# galvo_driver.net
KiCad netlist of a schematic drawn in Altium Designer
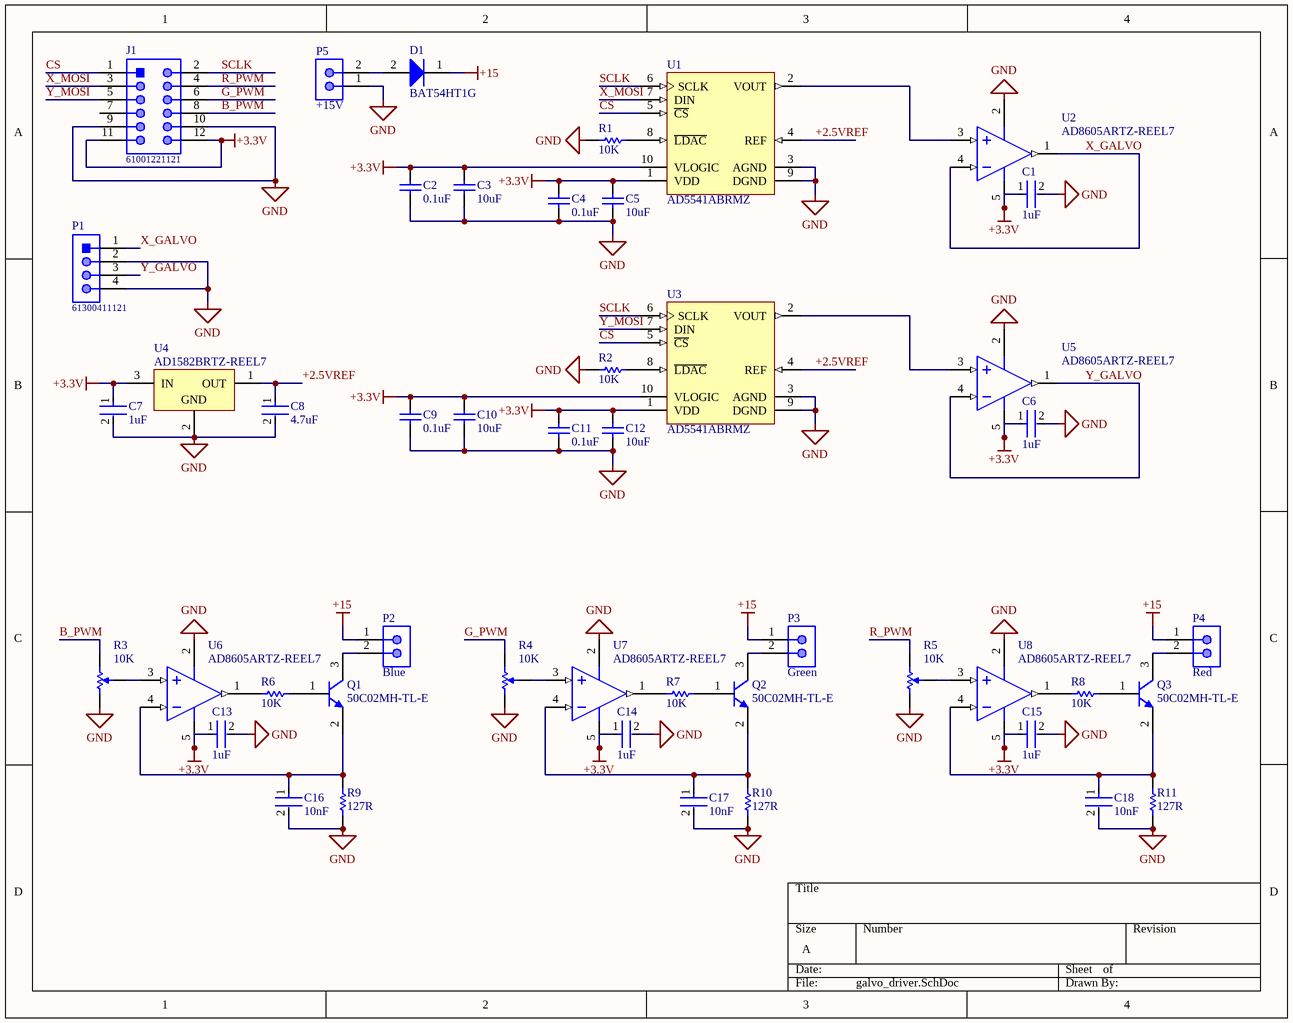
[diagram p0: galvo_driver.SchDoc]

(export (version "E")
  (design (tool "Eeschema 10.0.6"))
  (components
    (comp (ref "C1")
      (value "1uF")
      (footprint "FP-CC0603-DA-MFG")
      (description "CAP CER 1UF 16V X7R 0603")
      (fields (field (name "TOLERANCE") "0.1") (field (name "MANUFACTURER") "YAGEO"))
      (libsource (lib "Altium Content Vault") (part "11868f565c42a9108669ba33697ecf6"))
    )
    (comp (ref "C2")
      (value "0.1uF")
      (footprint "CAPC1608X87X35NL15T15")
      (description "C0603X104K5RACTU")
      (fields (field (name "MANUFACTURER") "Kemet"))
      (libsource (lib "Altium Content Vault") (part "CAP"))
    )
    (comp (ref "C3")
      (value "10uF")
      (footprint "CAPC1608X90X35NL10T15")
      (description "GRM188R60J106ME47D")
      (fields (field (name "MANUFACTURER") "Murata"))
      (libsource (lib "Altium Content Vault") (part "CAP"))
    )
    (comp (ref "C4")
      (value "0.1uF")
      (footprint "CAPC1608X87X35NL15T15")
      (description "C0603X104K5RACTU")
      (fields (field (name "MANUFACTURER") "Kemet"))
      (libsource (lib "Altium Content Vault") (part "CAP"))
    )
    (comp (ref "C5")
      (value "10uF")
      (footprint "CAPC1608X90X35NL10T15")
      (description "GRM188R60J106ME47D")
      (fields (field (name "MANUFACTURER") "Murata"))
      (libsource (lib "Altium Content Vault") (part "CAP"))
    )
    (comp (ref "C6")
      (value "1uF")
      (footprint "FP-CC0603-DA-MFG")
      (description "CAP CER 1UF 16V X7R 0603")
      (fields (field (name "TOLERANCE") "0.1") (field (name "MANUFACTURER") "YAGEO"))
      (libsource (lib "Altium Content Vault") (part "11868f565c42a9108669ba33697ecf6"))
    )
    (comp (ref "C7")
      (value "1uF")
      (footprint "FP-CC0603-DA-MFG")
      (description "CAP CER 1UF 16V X7R 0603")
      (fields (field (name "TOLERANCE") "0.1") (field (name "MANUFACTURER") "YAGEO"))
      (libsource (lib "Altium Content Vault") (part "11868f565c42a9108669ba33697ecf6"))
    )
    (comp (ref "C8")
      (value "4.7uF")
      (footprint "FP-C0603-CG-MFG")
      (description "CAP CER 4.7UF 6.3V X5R 0603")
      (fields (field (name "TOLERANCE") "10%") (field (name "MANUFACTURER") "Kemet"))
      (libsource (lib "Altium Content Vault") (part "11868f565c42a9108669ba33697ecf6"))
    )
    (comp (ref "C9")
      (value "0.1uF")
      (footprint "CAPC1608X87X35NL15T15")
      (description "C0603X104K5RACTU")
      (fields (field (name "MANUFACTURER") "Kemet"))
      (libsource (lib "Altium Content Vault") (part "CAP"))
    )
    (comp (ref "C10")
      (value "10uF")
      (footprint "CAPC1608X90X35NL10T15")
      (description "GRM188R60J106ME47D")
      (fields (field (name "MANUFACTURER") "Murata"))
      (libsource (lib "Altium Content Vault") (part "CAP"))
    )
    (comp (ref "C11")
      (value "0.1uF")
      (footprint "CAPC1608X87X35NL15T15")
      (description "C0603X104K5RACTU")
      (fields (field (name "MANUFACTURER") "Kemet"))
      (libsource (lib "Altium Content Vault") (part "CAP"))
    )
    (comp (ref "C12")
      (value "10uF")
      (footprint "CAPC1608X90X35NL10T15")
      (description "GRM188R60J106ME47D")
      (fields (field (name "MANUFACTURER") "Murata"))
      (libsource (lib "Altium Content Vault") (part "CAP"))
    )
    (comp (ref "C13")
      (value "1uF")
      (footprint "FP-CC0603-DA-MFG")
      (description "CAP CER 1UF 16V X7R 0603")
      (fields (field (name "TOLERANCE") "0.1") (field (name "MANUFACTURER") "YAGEO"))
      (libsource (lib "Altium Content Vault") (part "11868f565c42a9108669ba33697ecf6"))
    )
    (comp (ref "C14")
      (value "1uF")
      (footprint "FP-CC0603-DA-MFG")
      (description "CAP CER 1UF 16V X7R 0603")
      (fields (field (name "TOLERANCE") "0.1") (field (name "MANUFACTURER") "YAGEO"))
      (libsource (lib "Altium Content Vault") (part "11868f565c42a9108669ba33697ecf6"))
    )
    (comp (ref "C15")
      (value "1uF")
      (footprint "FP-CC0603-DA-MFG")
      (description "CAP CER 1UF 16V X7R 0603")
      (fields (field (name "TOLERANCE") "0.1") (field (name "MANUFACTURER") "YAGEO"))
      (libsource (lib "Altium Content Vault") (part "11868f565c42a9108669ba33697ecf6"))
    )
    (comp (ref "C16")
      (value "10nF")
      (footprint "FP-CGA3E-0_3-0_1-IPC_A")
      (description "Cap Ceramic 10nF 100V X8R 10% Pad SMD 0603 +150°C Automotive T/R")
      (fields (field (name "TOLERANCE") "10%"))
      (libsource (lib "Altium Content Vault") (part "b4654b650e69147ec39a6b967a45e02"))
    )
    (comp (ref "C17")
      (value "10nF")
      (footprint "FP-CGA3E-0_3-0_1-IPC_A")
      (description "Cap Ceramic 10nF 100V X8R 10% Pad SMD 0603 +150°C Automotive T/R")
      (fields (field (name "TOLERANCE") "10%"))
      (libsource (lib "Altium Content Vault") (part "b4654b650e69147ec39a6b967a45e02"))
    )
    (comp (ref "C18")
      (value "10nF")
      (footprint "FP-CGA3E-0_3-0_1-IPC_A")
      (description "Cap Ceramic 10nF 100V X8R 10% Pad SMD 0603 +150°C Automotive T/R")
      (fields (field (name "TOLERANCE") "10%"))
      (libsource (lib "Altium Content Vault") (part "b4654b650e69147ec39a6b967a45e02"))
    )
    (comp (ref "D1")
      (value "BAT54HT1G")
      (footprint "ONSC-SOD-323-2-477-02_V")
      (description "Schottky Barrier Diode, 2-Pin SOD-323, Pb-Free, Tape and Reel")
      (fields (field (name "MANUFACTURER") "On Semiconductor"))
      (libsource (lib "Altium Content Vault") (part "ONSC-D-K1A2-2"))
    )
    (comp (ref "J1")
      (value "61001221121")
      (footprint "61001221121")
      (description "SMT Vertical Pin Header WR-PHD, Pitch 2.54 mm, Dual Row, 12 pins")
      (fields (field (name "MANUFACTURER") "Wurth Elektronik") (field (name "PUBLISHER") "WurthElektronik"))
      (libsource (lib "Altium Content Vault") (part "WE-CN-2P-M-R12"))
    )
    (comp (ref "P1")
      (value "61300411121")
      (footprint "61300411121")
      (description "THT Vertical Pin Header WR-PHD, Pitch 2.54 mm, Single Row, 4 pins")
      (fields (field (name "MANUFACTURER") "Wurth Elektronik") (field (name "PUBLISHER") "WurthElektronik"))
      (libsource (lib "Altium Content Vault") (part "WE-CN-1P-M-R4"))
    )
    (comp (ref "P2")
      (value "Blue")
      (footprint "JST-B2B-XH-A_V")
      (fields (field (name "MANUFACTURER") "JST"))
      (libsource (lib "Altium Content Vault") (part "CN-1P-M-R2"))
    )
    (comp (ref "P3")
      (value "Green")
      (footprint "JST-B2B-XH-A_V")
      (fields (field (name "MANUFACTURER") "JST"))
      (libsource (lib "Altium Content Vault") (part "CN-1P-M-R2"))
    )
    (comp (ref "P4")
      (value "Red")
      (footprint "JST-B2B-XH-A_V")
      (fields (field (name "MANUFACTURER") "JST"))
      (libsource (lib "Altium Content Vault") (part "CN-1P-M-R2"))
    )
    (comp (ref "P5")
      (value "+15V")
      (footprint "JST-B2B-XH-A_V")
      (fields (field (name "MANUFACTURER") "JST"))
      (libsource (lib "") (part "CN-1P-M-R2_1"))
    )
    (comp (ref "Q1")
      (value "50C02MH-TL-E")
      (footprint "ONSC-MCPH-3_V")
      (description "Bipolar Transistor, 50 V, 0.5 A, Low VCE(sat), NPN Single, 3-Pin MCPH, Pb-Free, Tape and Reel")
      (fields (field (name "MANUFACTURER") "On Semiconductor"))
      (libsource (lib "Altium Content Vault") (part "ONSC-NPN-B1E2C3-3"))
    )
    (comp (ref "Q2")
      (value "50C02MH-TL-E")
      (footprint "ONSC-MCPH-3_V")
      (description "Bipolar Transistor, 50 V, 0.5 A, Low VCE(sat), NPN Single, 3-Pin MCPH, Pb-Free, Tape and Reel")
      (fields (field (name "MANUFACTURER") "On Semiconductor"))
      (libsource (lib "Altium Content Vault") (part "ONSC-NPN-B1E2C3-3"))
    )
    (comp (ref "Q3")
      (value "50C02MH-TL-E")
      (footprint "ONSC-MCPH-3_V")
      (description "Bipolar Transistor, 50 V, 0.5 A, Low VCE(sat), NPN Single, 3-Pin MCPH, Pb-Free, Tape and Reel")
      (fields (field (name "MANUFACTURER") "On Semiconductor"))
      (libsource (lib "Altium Content Vault") (part "ONSC-NPN-B1E2C3-3"))
    )
    (comp (ref "R1")
      (value "10K")
      (footprint "RESC1609X55X30LL15T15")
      (description "Chip Resistor, 10 KOhm, +/- 1%, 0.1 W, -55 to 155 degC, 0603 (1608 Metric), RoHS, Tape and Reel")
      (fields (field (name "TOLERANCE") "1%") (field (name "MANUFACTURER") "Panasonic"))
      (libsource (lib "Altium Content Vault") (part "RES-2"))
    )
    (comp (ref "R2")
      (value "10K")
      (footprint "RESC1609X55X30LL15T15")
      (description "Chip Resistor, 10 KOhm, +/- 1%, 0.1 W, -55 to 155 degC, 0603 (1608 Metric), RoHS, Tape and Reel")
      (fields (field (name "TOLERANCE") "1%") (field (name "MANUFACTURER") "Panasonic"))
      (libsource (lib "Altium Content Vault") (part "RES-2"))
    )
    (comp (ref "R3")
      (value "10K")
      (footprint "BOUR-3313J-1_V")
      (description "Trimming Potentiometer, 10 KOhm, -55 to 125 degC, 3-Pin SMD, RoHS, Tape and Reel")
      (fields (field (name "MANUFACTURER") "Bourns"))
      (libsource (lib "Altium Content Vault") (part "RES-ADJ-3_A"))
    )
    (comp (ref "R4")
      (value "10K")
      (footprint "BOUR-3313J-1_V")
      (description "Trimming Potentiometer, 10 KOhm, -55 to 125 degC, 3-Pin SMD, RoHS, Tape and Reel")
      (fields (field (name "MANUFACTURER") "Bourns"))
      (libsource (lib "Altium Content Vault") (part "RES-ADJ-3_A"))
    )
    (comp (ref "R5")
      (value "10K")
      (footprint "BOUR-3313J-1_V")
      (description "Trimming Potentiometer, 10 KOhm, -55 to 125 degC, 3-Pin SMD, RoHS, Tape and Reel")
      (fields (field (name "MANUFACTURER") "Bourns"))
      (libsource (lib "Altium Content Vault") (part "RES-ADJ-3_A"))
    )
    (comp (ref "R6")
      (value "10K")
      (footprint "RESC1609X55X30LL15T15")
      (description "Chip Resistor, 10 KOhm, +/- 1%, 0.1 W, -55 to 155 degC, 0603 (1608 Metric), RoHS, Tape and Reel")
      (fields (field (name "TOLERANCE") "1%") (field (name "MANUFACTURER") "Panasonic"))
      (libsource (lib "Altium Content Vault") (part "RES-2"))
    )
    (comp (ref "R7")
      (value "10K")
      (footprint "RESC1609X55X30LL15T15")
      (description "Chip Resistor, 10 KOhm, +/- 1%, 0.1 W, -55 to 155 degC, 0603 (1608 Metric), RoHS, Tape and Reel")
      (fields (field (name "TOLERANCE") "1%") (field (name "MANUFACTURER") "Panasonic"))
      (libsource (lib "Altium Content Vault") (part "RES-2"))
    )
    (comp (ref "R8")
      (value "10K")
      (footprint "RESC1609X55X30LL15T15")
      (description "Chip Resistor, 10 KOhm, +/- 1%, 0.1 W, -55 to 155 degC, 0603 (1608 Metric), RoHS, Tape and Reel")
      (fields (field (name "TOLERANCE") "1%") (field (name "MANUFACTURER") "Panasonic"))
      (libsource (lib "Altium Content Vault") (part "RES-2"))
    )
    (comp (ref "R9")
      (value "127R")
      (footprint "RESC1608X55X30LL15T15")
      (description "ERJ-3EKF1270V")
      (fields (field (name "MANUFACTURER") "Panasonic"))
      (libsource (lib "Altium Content Vault") (part "RES"))
    )
    (comp (ref "R10")
      (value "127R")
      (footprint "RESC1608X55X30LL15T15")
      (description "ERJ-3EKF1270V")
      (fields (field (name "MANUFACTURER") "Panasonic"))
      (libsource (lib "Altium Content Vault") (part "RES"))
    )
    (comp (ref "R11")
      (value "127R")
      (footprint "RESC1608X55X30LL15T15")
      (description "ERJ-3EKF1270V")
      (fields (field (name "MANUFACTURER") "Panasonic"))
      (libsource (lib "Altium Content Vault") (part "RES"))
    )
    (comp (ref "U1")
      (value "AD5541ABRMZ")
      (footprint "RM-10_L")
      (fields (field (name "GENERIC PART NUMBER") "AD5541A") (field (name "MANUFACTURER") "Analog Devices"))
      (libsource (lib "Altium Content Vault") (part "ADI-AD5541A-RM-10"))
    )
    (comp (ref "U2")
      (value "AD8605ARTZ-REEL7")
      (footprint "ADI-RJ-5_M")
      (fields (field (name "MANUFACTURER") "Analog Devices") (field (name "GENERIC PART NUMBER") "AD8605"))
      (libsource (lib "Altium Content Vault") (part "ADI-ADxxxx-X-5"))
    )
    (comp (ref "U3")
      (value "AD5541ABRMZ")
      (footprint "RM-10_L")
      (fields (field (name "GENERIC PART NUMBER") "AD5541A") (field (name "MANUFACTURER") "Analog Devices"))
      (libsource (lib "Altium Content Vault") (part "ADI-AD5541A-RM-10"))
    )
    (comp (ref "U4")
      (value "AD1582BRTZ-REEL7")
      (footprint "ADI-RT-3_M")
      (fields (field (name "MANUFACTURER") "Analog Devices"))
      (libsource (lib "Altium Content Vault") (part "ADI-AD158X-RT-3"))
    )
    (comp (ref "U5")
      (value "AD8605ARTZ-REEL7")
      (footprint "ADI-RJ-5_M")
      (fields (field (name "MANUFACTURER") "Analog Devices") (field (name "GENERIC PART NUMBER") "AD8605"))
      (libsource (lib "Altium Content Vault") (part "ADI-ADxxxx-X-5"))
    )
    (comp (ref "U6")
      (value "AD8605ARTZ-REEL7")
      (footprint "ADI-RJ-5_M")
      (fields (field (name "MANUFACTURER") "Analog Devices") (field (name "GENERIC PART NUMBER") "AD8605"))
      (libsource (lib "Altium Content Vault") (part "ADI-ADxxxx-X-5"))
    )
    (comp (ref "U7")
      (value "AD8605ARTZ-REEL7")
      (footprint "ADI-RJ-5_M")
      (fields (field (name "MANUFACTURER") "Analog Devices") (field (name "GENERIC PART NUMBER") "AD8605"))
      (libsource (lib "Altium Content Vault") (part "ADI-ADxxxx-X-5"))
    )
    (comp (ref "U8")
      (value "AD8605ARTZ-REEL7")
      (footprint "ADI-RJ-5_M")
      (fields (field (name "MANUFACTURER") "Analog Devices") (field (name "GENERIC PART NUMBER") "AD8605"))
      (libsource (lib "Altium Content Vault") (part "ADI-ADxxxx-X-5"))
    )
  )
  (nets
    (net (code "1") (name "+3.3V") (class "Default")
      (node (ref "C1") (pin "1") (pinfunction "1_1") (pintype "passive"))
      (node (ref "C10") (pin "2") (pinfunction "2_2") (pintype "passive"))
      (node (ref "C11") (pin "1") (pinfunction "1_1") (pintype "passive"))
      (node (ref "C12") (pin "2") (pinfunction "2_2") (pintype "passive"))
      (node (ref "C13") (pin "1") (pinfunction "1_1") (pintype "passive"))
      (node (ref "C14") (pin "1") (pinfunction "1_1") (pintype "passive"))
      (node (ref "C15") (pin "1") (pinfunction "1_1") (pintype "passive"))
      (node (ref "C2") (pin "1") (pinfunction "1_1") (pintype "passive"))
      (node (ref "C3") (pin "2") (pinfunction "2_2") (pintype "passive"))
      (node (ref "C4") (pin "1") (pinfunction "1_1") (pintype "passive"))
      (node (ref "C5") (pin "2") (pinfunction "2_2") (pintype "passive"))
      (node (ref "C6") (pin "1") (pinfunction "1_1") (pintype "passive"))
      (node (ref "C7") (pin "1") (pinfunction "1_1") (pintype "passive"))
      (node (ref "C9") (pin "1") (pinfunction "1_1") (pintype "passive"))
      (node (ref "J1") (pin "11") (pinfunction "11_11") (pintype "passive"))
      (node (ref "J1") (pin "12") (pinfunction "12_12") (pintype "passive"))
      (node (ref "U1") (pin "1") (pinfunction "VDD_1") (pintype "power_in"))
      (node (ref "U1") (pin "10") (pinfunction "VLOGIC_10") (pintype "power_in"))
      (node (ref "U2") (pin "5") (pinfunction "+V_5") (pintype "power_in"))
      (node (ref "U3") (pin "1") (pinfunction "VDD_1") (pintype "power_in"))
      (node (ref "U3") (pin "10") (pinfunction "VLOGIC_10") (pintype "power_in"))
      (node (ref "U4") (pin "3") (pinfunction "IN_3") (pintype "power_in"))
      (node (ref "U5") (pin "5") (pinfunction "+V_5") (pintype "power_in"))
      (node (ref "U6") (pin "5") (pinfunction "+V_5") (pintype "power_in"))
      (node (ref "U7") (pin "5") (pinfunction "+V_5") (pintype "power_in"))
      (node (ref "U8") (pin "5") (pinfunction "+V_5") (pintype "power_in"))
    )
    (net (code "2") (name "+15") (class "Default")
      (node (ref "D1") (pin "1") (pinfunction "K_1") (pintype "passive"))
      (node (ref "P2") (pin "1") (pinfunction "1_1") (pintype "passive"))
      (node (ref "P3") (pin "1") (pinfunction "1_1") (pintype "passive"))
      (node (ref "P4") (pin "1") (pinfunction "1_1") (pintype "passive"))
    )
    (net (code "3") (name "/+2.5VREF") (class "Default")
      (node (ref "C8") (pin "1") (pinfunction "1_1") (pintype "passive"))
      (node (ref "U1") (pin "4") (pinfunction "REF_4") (pintype "input"))
      (node (ref "U3") (pin "4") (pinfunction "REF_4") (pintype "input"))
      (node (ref "U4") (pin "1") (pinfunction "OUT_1") (pintype "power_in"))
    )
    (net (code "4") (name "/B_PWM") (class "Default")
      (node (ref "J1") (pin "8") (pinfunction "8_8") (pintype "passive"))
      (node (ref "R3") (pin "3") (pinfunction "3_3") (pintype "passive"))
    )
    (net (code "5") (name "/CS") (class "Default")
      (node (ref "J1") (pin "1") (pinfunction "1_1") (pintype "passive"))
      (node (ref "U1") (pin "5") (pinfunction "~{CS}_5") (pintype "input"))
      (node (ref "U3") (pin "5") (pinfunction "~{CS}_5") (pintype "input"))
    )
    (net (code "6") (name "/G_PWM") (class "Default")
      (node (ref "J1") (pin "6") (pinfunction "6_6") (pintype "passive"))
      (node (ref "R4") (pin "3") (pinfunction "3_3") (pintype "passive"))
    )
    (net (code "7") (name "/R_PWM") (class "Default")
      (node (ref "J1") (pin "4") (pinfunction "4_4") (pintype "passive"))
      (node (ref "R5") (pin "3") (pinfunction "3_3") (pintype "passive"))
    )
    (net (code "8") (name "/SCLK") (class "Default")
      (node (ref "J1") (pin "2") (pinfunction "2_2") (pintype "passive"))
      (node (ref "U1") (pin "6") (pinfunction "SCLK_6") (pintype "input"))
      (node (ref "U3") (pin "6") (pinfunction "SCLK_6") (pintype "input"))
    )
    (net (code "9") (name "/X_GALVO") (class "Default")
      (node (ref "P1") (pin "1") (pinfunction "1_1") (pintype "passive"))
      (node (ref "U2") (pin "1") (pinfunction "OUT_1") (pintype "output"))
      (node (ref "U2") (pin "4") (pinfunction "-IN_4") (pintype "input"))
    )
    (net (code "10") (name "/X_MOSI") (class "Default")
      (node (ref "J1") (pin "3") (pinfunction "3_3") (pintype "passive"))
      (node (ref "U1") (pin "7") (pinfunction "DIN_7") (pintype "input"))
    )
    (net (code "11") (name "/Y_GALVO") (class "Default")
      (node (ref "P1") (pin "3") (pinfunction "3_3") (pintype "passive"))
      (node (ref "U5") (pin "1") (pinfunction "OUT_1") (pintype "output"))
      (node (ref "U5") (pin "4") (pinfunction "-IN_4") (pintype "input"))
    )
    (net (code "12") (name "/Y_MOSI") (class "Default")
      (node (ref "J1") (pin "5") (pinfunction "5_5") (pintype "passive"))
      (node (ref "U3") (pin "7") (pinfunction "DIN_7") (pintype "input"))
    )
    (net (code "13") (name "GND") (class "Default")
      (node (ref "C1") (pin "2") (pinfunction "2_2") (pintype "passive"))
      (node (ref "C10") (pin "1") (pinfunction "1_1") (pintype "passive"))
      (node (ref "C11") (pin "2") (pinfunction "2_2") (pintype "passive"))
      (node (ref "C12") (pin "1") (pinfunction "1_1") (pintype "passive"))
      (node (ref "C13") (pin "2") (pinfunction "2_2") (pintype "passive"))
      (node (ref "C14") (pin "2") (pinfunction "2_2") (pintype "passive"))
      (node (ref "C15") (pin "2") (pinfunction "2_2") (pintype "passive"))
      (node (ref "C16") (pin "2") (pinfunction "2_2") (pintype "passive"))
      (node (ref "C17") (pin "2") (pinfunction "2_2") (pintype "passive"))
      (node (ref "C18") (pin "2") (pinfunction "2_2") (pintype "passive"))
      (node (ref "C2") (pin "2") (pinfunction "2_2") (pintype "passive"))
      (node (ref "C3") (pin "1") (pinfunction "1_1") (pintype "passive"))
      (node (ref "C4") (pin "2") (pinfunction "2_2") (pintype "passive"))
      (node (ref "C5") (pin "1") (pinfunction "1_1") (pintype "passive"))
      (node (ref "C6") (pin "2") (pinfunction "2_2") (pintype "passive"))
      (node (ref "C7") (pin "2") (pinfunction "2_2") (pintype "passive"))
      (node (ref "C8") (pin "2") (pinfunction "2_2") (pintype "passive"))
      (node (ref "C9") (pin "2") (pinfunction "2_2") (pintype "passive"))
      (node (ref "J1") (pin "10") (pinfunction "10_10") (pintype "passive"))
      (node (ref "J1") (pin "9") (pinfunction "9_9") (pintype "passive"))
      (node (ref "P1") (pin "2") (pinfunction "2_2") (pintype "passive"))
      (node (ref "P1") (pin "4") (pinfunction "4_4") (pintype "passive"))
      (node (ref "P5") (pin "1") (pinfunction "1_1") (pintype "passive"))
      (node (ref "R1") (pin "2") (pinfunction "2_2") (pintype "passive"))
      (node (ref "R10") (pin "1") (pinfunction "1_1") (pintype "passive"))
      (node (ref "R11") (pin "1") (pinfunction "1_1") (pintype "passive"))
      (node (ref "R2") (pin "2") (pinfunction "2_2") (pintype "passive"))
      (node (ref "R3") (pin "1") (pinfunction "1_1") (pintype "passive"))
      (node (ref "R4") (pin "1") (pinfunction "1_1") (pintype "passive"))
      (node (ref "R5") (pin "1") (pinfunction "1_1") (pintype "passive"))
      (node (ref "R9") (pin "1") (pinfunction "1_1") (pintype "passive"))
      (node (ref "U1") (pin "3") (pinfunction "AGND_3") (pintype "power_in"))
      (node (ref "U1") (pin "9") (pinfunction "DGND_9") (pintype "power_in"))
      (node (ref "U2") (pin "2") (pinfunction "-V_2") (pintype "power_in"))
      (node (ref "U3") (pin "3") (pinfunction "AGND_3") (pintype "power_in"))
      (node (ref "U3") (pin "9") (pinfunction "DGND_9") (pintype "power_in"))
      (node (ref "U4") (pin "2") (pinfunction "GND_2") (pintype "power_in"))
      (node (ref "U5") (pin "2") (pinfunction "-V_2") (pintype "power_in"))
      (node (ref "U6") (pin "2") (pinfunction "-V_2") (pintype "power_in"))
      (node (ref "U7") (pin "2") (pinfunction "-V_2") (pintype "power_in"))
      (node (ref "U8") (pin "2") (pinfunction "-V_2") (pintype "power_in"))
    )
    (net (code "14") (name "Net-(D1-A)") (class "Default")
      (node (ref "D1") (pin "2") (pinfunction "A_2") (pintype "passive"))
      (node (ref "P5") (pin "2") (pinfunction "2_2") (pintype "passive"))
    )
    (net (code "15") (name "Net-(Q1-B)") (class "Default")
      (node (ref "Q1") (pin "1") (pinfunction "B_1") (pintype "passive"))
      (node (ref "R6") (pin "2") (pinfunction "2_2") (pintype "passive"))
    )
    (net (code "16") (name "Net-(Q1-C)") (class "Default")
      (node (ref "P2") (pin "2") (pinfunction "2_2") (pintype "passive"))
      (node (ref "Q1") (pin "3") (pinfunction "C_3") (pintype "passive"))
    )
    (net (code "17") (name "Net-(Q1-E)") (class "Default")
      (node (ref "C16") (pin "1") (pinfunction "1_1") (pintype "passive"))
      (node (ref "Q1") (pin "2") (pinfunction "E_2") (pintype "passive"))
      (node (ref "R9") (pin "2") (pinfunction "2_2") (pintype "passive"))
      (node (ref "U6") (pin "4") (pinfunction "-IN_4") (pintype "input"))
    )
    (net (code "18") (name "Net-(Q2-B)") (class "Default")
      (node (ref "Q2") (pin "1") (pinfunction "B_1") (pintype "passive"))
      (node (ref "R7") (pin "2") (pinfunction "2_2") (pintype "passive"))
    )
    (net (code "19") (name "Net-(Q2-C)") (class "Default")
      (node (ref "P3") (pin "2") (pinfunction "2_2") (pintype "passive"))
      (node (ref "Q2") (pin "3") (pinfunction "C_3") (pintype "passive"))
    )
    (net (code "20") (name "Net-(Q2-E)") (class "Default")
      (node (ref "C17") (pin "1") (pinfunction "1_1") (pintype "passive"))
      (node (ref "Q2") (pin "2") (pinfunction "E_2") (pintype "passive"))
      (node (ref "R10") (pin "2") (pinfunction "2_2") (pintype "passive"))
      (node (ref "U7") (pin "4") (pinfunction "-IN_4") (pintype "input"))
    )
    (net (code "21") (name "Net-(Q3-B)") (class "Default")
      (node (ref "Q3") (pin "1") (pinfunction "B_1") (pintype "passive"))
      (node (ref "R8") (pin "2") (pinfunction "2_2") (pintype "passive"))
    )
    (net (code "22") (name "Net-(Q3-C)") (class "Default")
      (node (ref "P4") (pin "2") (pinfunction "2_2") (pintype "passive"))
      (node (ref "Q3") (pin "3") (pinfunction "C_3") (pintype "passive"))
    )
    (net (code "23") (name "Net-(Q3-E)") (class "Default")
      (node (ref "C18") (pin "1") (pinfunction "1_1") (pintype "passive"))
      (node (ref "Q3") (pin "2") (pinfunction "E_2") (pintype "passive"))
      (node (ref "R11") (pin "2") (pinfunction "2_2") (pintype "passive"))
      (node (ref "U8") (pin "4") (pinfunction "-IN_4") (pintype "input"))
    )
    (net (code "24") (name "Net-(U1-VOUT)") (class "Default")
      (node (ref "U1") (pin "2") (pinfunction "VOUT_2") (pintype "output"))
      (node (ref "U2") (pin "3") (pinfunction "+IN_3") (pintype "input"))
    )
    (net (code "25") (name "Net-(U1-~{LDAC})") (class "Default")
      (node (ref "R1") (pin "1") (pinfunction "1_1") (pintype "passive"))
      (node (ref "U1") (pin "8") (pinfunction "~{LDAC}_8") (pintype "input"))
    )
    (net (code "26") (name "Net-(U3-VOUT)") (class "Default")
      (node (ref "U3") (pin "2") (pinfunction "VOUT_2") (pintype "output"))
      (node (ref "U5") (pin "3") (pinfunction "+IN_3") (pintype "input"))
    )
    (net (code "27") (name "Net-(U3-~{LDAC})") (class "Default")
      (node (ref "R2") (pin "1") (pinfunction "1_1") (pintype "passive"))
      (node (ref "U3") (pin "8") (pinfunction "~{LDAC}_8") (pintype "input"))
    )
    (net (code "28") (name "Net-(U6-+IN)") (class "Default")
      (node (ref "R3") (pin "2") (pinfunction "2_2") (pintype "passive"))
      (node (ref "U6") (pin "3") (pinfunction "+IN_3") (pintype "input"))
    )
    (net (code "29") (name "Net-(U6-OUT)") (class "Default")
      (node (ref "R6") (pin "1") (pinfunction "1_1") (pintype "passive"))
      (node (ref "U6") (pin "1") (pinfunction "OUT_1") (pintype "output"))
    )
    (net (code "30") (name "Net-(U7-+IN)") (class "Default")
      (node (ref "R4") (pin "2") (pinfunction "2_2") (pintype "passive"))
      (node (ref "U7") (pin "3") (pinfunction "+IN_3") (pintype "input"))
    )
    (net (code "31") (name "Net-(U7-OUT)") (class "Default")
      (node (ref "R7") (pin "1") (pinfunction "1_1") (pintype "passive"))
      (node (ref "U7") (pin "1") (pinfunction "OUT_1") (pintype "output"))
    )
    (net (code "32") (name "Net-(U8-+IN)") (class "Default")
      (node (ref "R5") (pin "2") (pinfunction "2_2") (pintype "passive"))
      (node (ref "U8") (pin "3") (pinfunction "+IN_3") (pintype "input"))
    )
    (net (code "33") (name "Net-(U8-OUT)") (class "Default")
      (node (ref "R8") (pin "1") (pinfunction "1_1") (pintype "passive"))
      (node (ref "U8") (pin "1") (pinfunction "OUT_1") (pintype "output"))
    )
    (net (code "34") (name "unconnected-(J1-Pad7)") (class "Default")
      (node (ref "J1") (pin "7") (pinfunction "7_7") (pintype "passive"))
    )
  )
)
